# GENERADORA_V1_5.net
KiCad netlist of a schematic drawn in Altium Designer
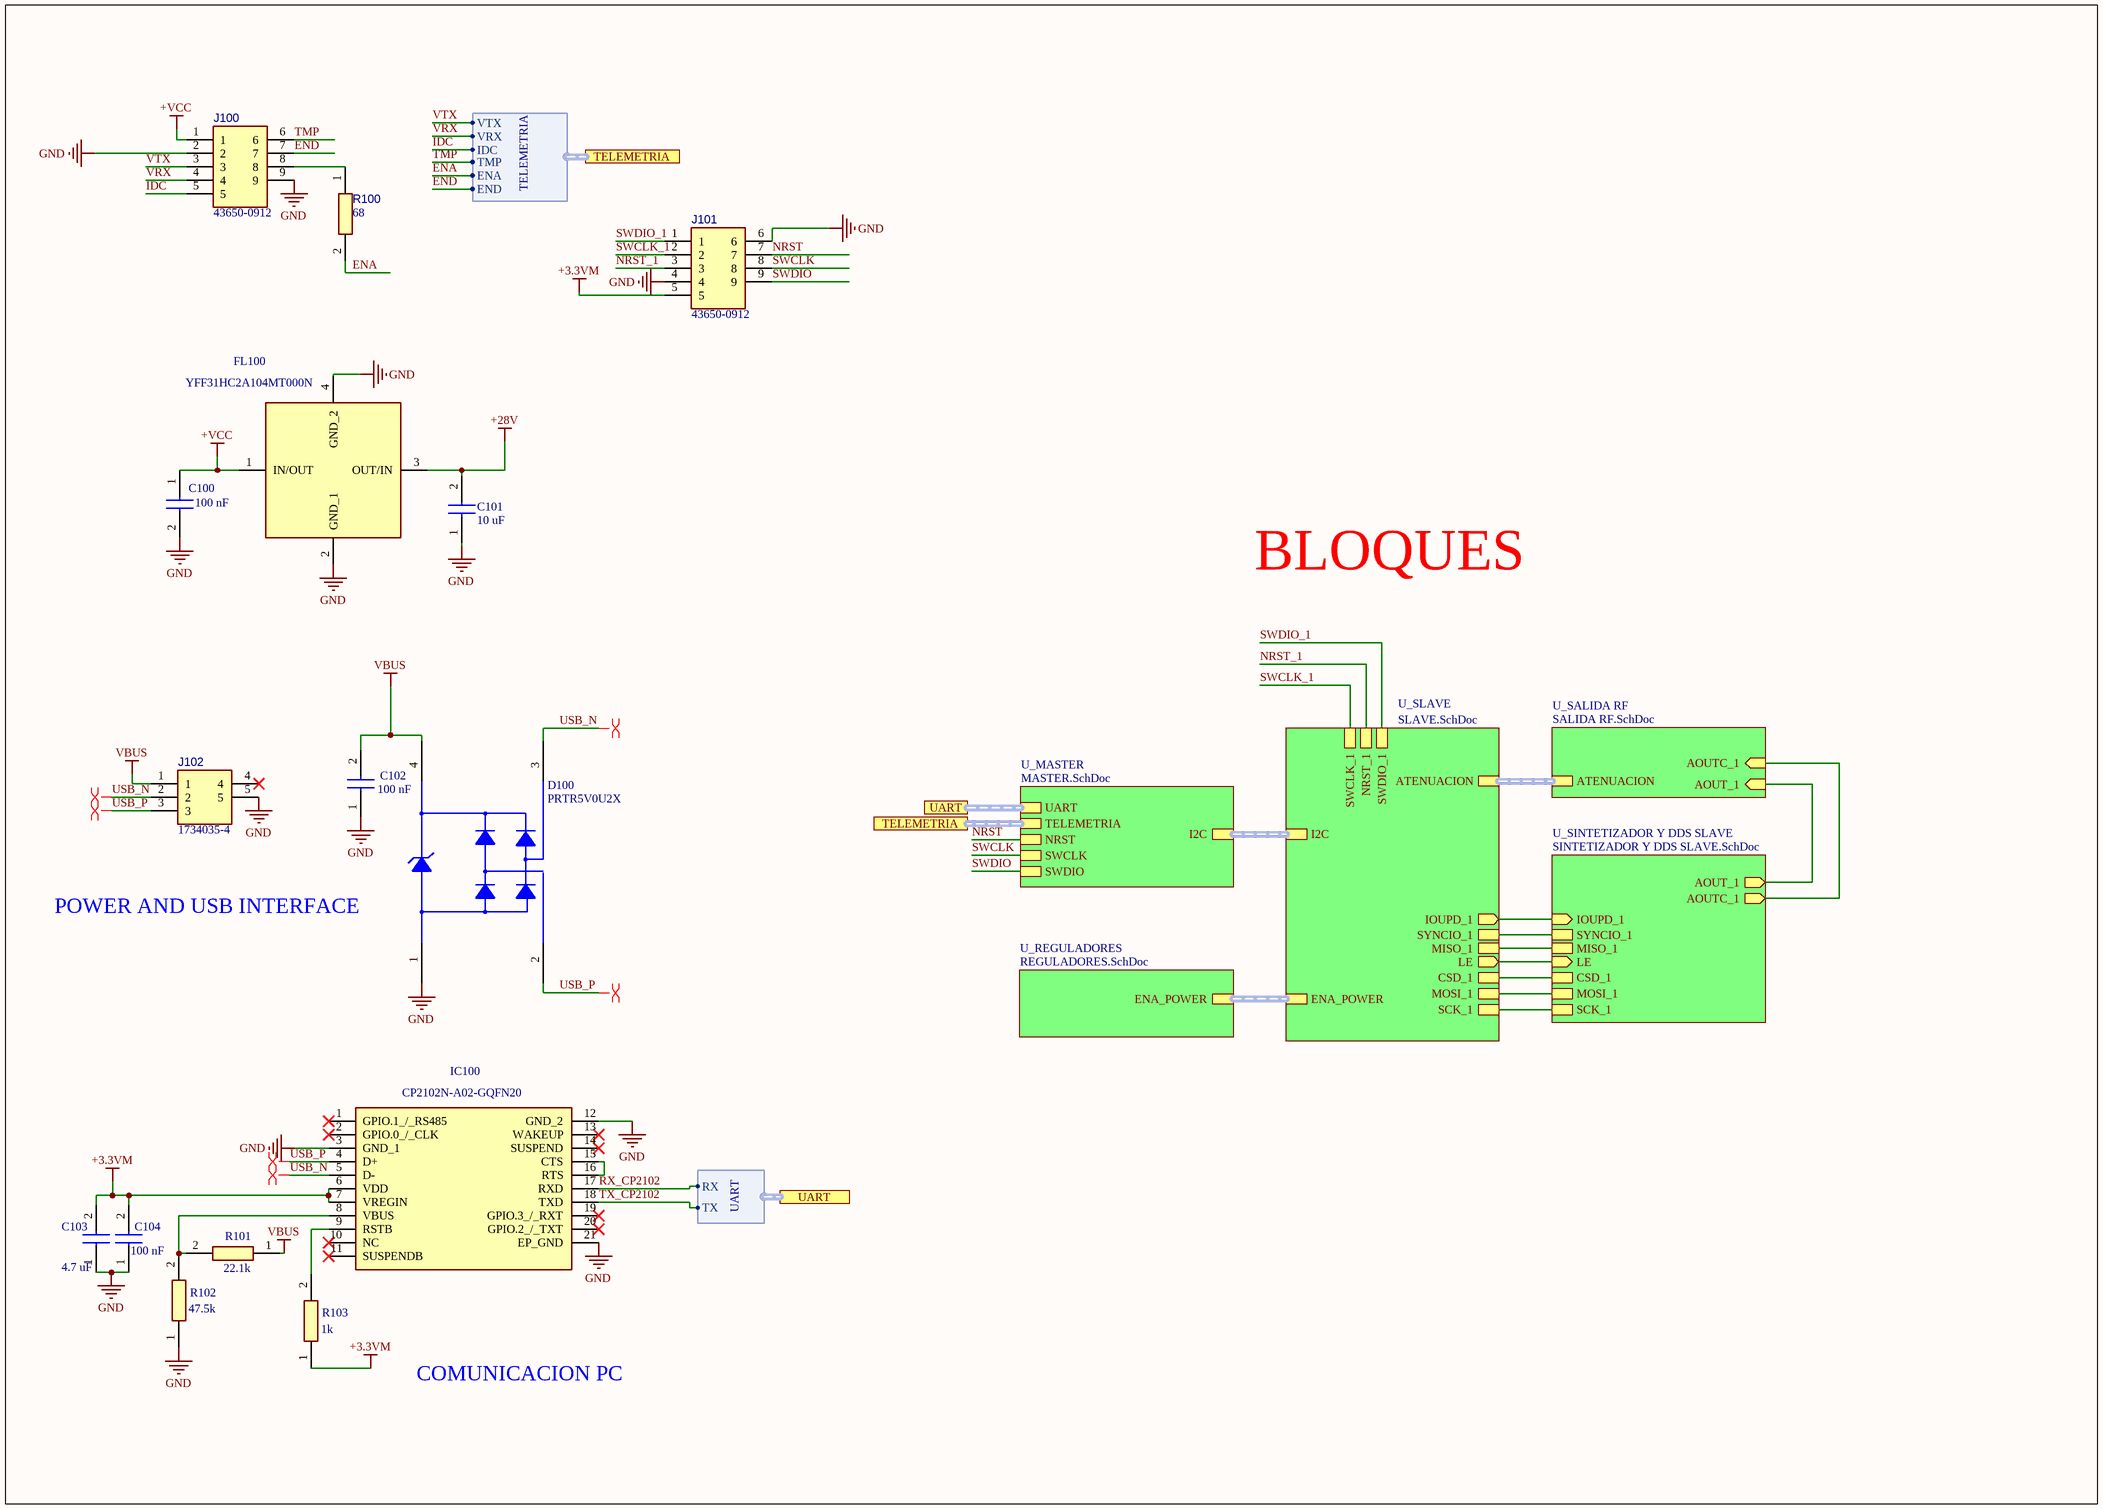
[diagram p0: GENERADORA V1.5.SchDoc]

(export (version "E")
  (design (tool "Eeschema 10.0.6"))
  (components
    (comp (ref "C100")
      (value "100 nF")
      (footprint "SamacSys:CAPC3216X94N")
      (description "Capacitor")
      (fields
        (field (name "MANUFACTURER_PART_NUMBER") "KAM31BR81H103KT")
        (field (name "MOUSER PART NUMBER") "581-KAM31BR81H103KT")
      )
      (libsource (lib "LIBRERIA_GEN_V2.0") (part "KAM31BR81H103KT"))
    )
    (comp (ref "C101")
      (value "10 uF")
      (footprint "SamacSys:CAPC3216X94N")
      (description "Capacitor")
      (fields
        (field (name "MANUFACTURER_PART_NUMBER") "KAM31BR81H103KT")
        (field (name "MOUSER PART NUMBER") "581-KAM31BR81H103KT")
      )
      (libsource (lib "LIBRERIA_GEN_V2.0") (part "KAM31BR81H103KT"))
    )
    (comp (ref "C102")
      (value "100 nF")
      (footprint "SamacSys:CAPC3216X94N")
      (description "Capacitor")
      (fields
        (field (name "MANUFACTURER_PART_NUMBER") "KAM31BR81H103KT")
        (field (name "MOUSER PART NUMBER") "581-KAM31BR81H103KT")
      )
      (libsource (lib "LIBRERIA_GEN_V2.0") (part "KAM31BR81H103KT"))
    )
    (comp (ref "C103")
      (value "4.7 uF")
      (footprint "SamacSys:C0603")
      (description "Capacitor")
      (fields (field (name "MANUFACTURER_PART_NUMBER") "C0603H470J5GACTU"))
      (libsource (lib "LIBRERIA_GEN_V2.0") (part "C0603H470J5GACTU"))
    )
    (comp (ref "C104")
      (value "100 nF")
      (footprint "SamacSys:C0603")
      (description "Capacitor")
      (fields (field (name "MANUFACTURER_PART_NUMBER") "C0603H470J5GACTU"))
      (libsource (lib "LIBRERIA_GEN_V2.0") (part "C0603H470J5GACTU"))
    )
    (comp (ref "D100")
      (value "PRTR5V0U2X")
      (footprint "AP4-00001")
      (description "Double rail-to-rail USB ESD protection diode")
      (fields (field (name "MANUFACTURER") "Philips"))
      (libsource (lib "SAM4S_Xplained_Pro") (part "PRTR5V0U2X"))
    )
    (comp (ref "FL100")
      (value "YFF31HC2A104MT000N")
      (footprint "SamacSys:YFF31HC2A104MT000N")
      (description "Filter")
      (fields (field (name "MOUSER PART NUMBER") "810-YFF31HC2A104MTHN"))
      (libsource (lib "LIBRERIA_GEN_V2.0") (part "YFF31HC2A104MT000N"))
    )
    (comp (ref "IC100")
      (value "CP2102N-A02-GQFN20")
      (footprint "SamacSys:CP2102NA02GQFN20")
      (description "Integrated Circuit")
      (fields (field (name "MOUSER PART NUMBER") "634-CP2102NA02GQFN20"))
      (libsource (lib "LIBRERIA_GEN_V2.0") (part "CP2102N-A02-GQFN20"))
    )
    (comp (ref "J100")
      (value "43650-0912")
      (footprint "SamacSys:43650-09(12,13,14)")
      (description "Connector")
      (fields (field (name "MOUSER PART NUMBER") "538-43650-0912"))
      (libsource (lib "*") (part "43650-0912"))
    )
    (comp (ref "J101")
      (value "43650-0912")
      (footprint "SamacSys:43650-09(12,13,14)")
      (description "Connector")
      (fields (field (name "MOUSER PART NUMBER") "538-43650-0912"))
      (libsource (lib "*") (part "43650-0912"))
    )
    (comp (ref "J102")
      (value "1734035-4")
      (footprint "SamacSys:1734035-2USB")
      (description "Connector")
      (fields (field (name "MOUSER PART NUMBER") "571-1734035-4"))
      (libsource (lib "SamacSys") (part "1734035-4"))
    )
    (comp (ref "R100")
      (value "68")
      (footprint "SamacSys:RESC1608X55N")
      (description "Resistor")
      (fields
        (field (name "MANUFACTURER_PART_NUMBER") "CR0603-FX-1431ELF")
        (field (name "MOUSER PART NUMBER") "652-CR0603FX-1431ELF")
      )
      (libsource (lib "*") (part "CR0603-FX-1431ELF"))
    )
    (comp (ref "R101")
      (value "22.1k")
      (footprint "SamacSys:RESC1608X55N")
      (description "Resistor")
      (fields
        (field (name "MANUFACTURER_PART_NUMBER") "CR0603-FX-1431ELF")
        (field (name "MOUSER PART NUMBER") "652-CR0603FX-1431ELF")
      )
      (libsource (lib "") (part "CR0603-FX-1431ELF_1"))
    )
    (comp (ref "R102")
      (value "47.5k")
      (footprint "SamacSys:RESC1608X55N")
      (description "Resistor")
      (fields
        (field (name "MANUFACTURER_PART_NUMBER") "CR0603-FX-1431ELF")
        (field (name "MOUSER PART NUMBER") "652-CR0603FX-1431ELF")
      )
      (libsource (lib "LIBRERIA_GEN_V2.0") (part "CR0603-FX-1431ELF"))
    )
    (comp (ref "R103")
      (value "1k")
      (footprint "SamacSys:RESC1608X55N")
      (description "Resistor")
      (fields
        (field (name "MANUFACTURER_PART_NUMBER") "CR0603-FX-1431ELF")
        (field (name "MOUSER PART NUMBER") "652-CR0603FX-1431ELF")
      )
      (libsource (lib "LIBRERIA_GEN_V2.0") (part "CR0603-FX-1431ELF"))
    )
  )
  (nets
    (net (code "4") (name "+3.3VM") (class "Default")
      (node (ref "C103") (pin "2") (pinfunction "2_2") (pintype "passive"))
      (node (ref "C104") (pin "2") (pinfunction "2_2") (pintype "passive"))
      (node (ref "IC100") (pin "6") (pinfunction "VDD_6") (pintype "passive"))
      (node (ref "IC100") (pin "7") (pinfunction "VREGIN_7") (pintype "passive"))
      (node (ref "J101") (pin "5") (pinfunction "5_5") (pintype "passive"))
      (node (ref "R103") (pin "1") (pinfunction "1_1") (pintype "passive"))
    )
    (net (code "5") (name "+28V") (class "Default")
      (node (ref "C101") (pin "2") (pinfunction "2_2") (pintype "passive"))
      (node (ref "FL100") (pin "3") (pinfunction "OUT/IN_3") (pintype "passive"))
    )
    (net (code "6") (name "+VCC") (class "Default")
      (node (ref "C100") (pin "1") (pinfunction "1_1") (pintype "passive"))
      (node (ref "FL100") (pin "1") (pinfunction "IN/OUT_1") (pintype "passive"))
      (node (ref "J100") (pin "1") (pinfunction "1_1") (pintype "passive"))
    )
    (net (code "11") (name "/ENA") (class "Default")
      (node (ref "R100") (pin "2") (pinfunction "2_2") (pintype "passive"))
    )
    (net (code "13") (name "/END") (class "Default")
      (node (ref "J100") (pin "7") (pinfunction "7_7") (pintype "passive"))
    )
    (net (code "15") (name "/IDC") (class "Default")
      (node (ref "J100") (pin "5") (pinfunction "5_5") (pintype "passive"))
    )
    (net (code "20") (name "/NRST") (class "Default")
      (node (ref "J101") (pin "7") (pinfunction "7_7") (pintype "passive"))
    )
    (net (code "21") (name "/NRST_1") (class "Default")
      (node (ref "J101") (pin "3") (pinfunction "3_3") (pintype "passive"))
    )
    (net (code "22") (name "/RX_CP2102") (class "Default")
      (node (ref "IC100") (pin "17") (pinfunction "RXD_17") (pintype "passive"))
    )
    (net (code "24") (name "/SWCLK") (class "Default")
      (node (ref "J101") (pin "8") (pinfunction "8_8") (pintype "passive"))
    )
    (net (code "25") (name "/SWCLK_1") (class "Default")
      (node (ref "J101") (pin "2") (pinfunction "2_2") (pintype "passive"))
    )
    (net (code "26") (name "/SWDIO") (class "Default")
      (node (ref "J101") (pin "9") (pinfunction "9_9") (pintype "passive"))
    )
    (net (code "27") (name "/SWDIO_1") (class "Default")
      (node (ref "J101") (pin "1") (pinfunction "1_1") (pintype "passive"))
    )
    (net (code "29") (name "/TMP") (class "Default")
      (node (ref "J100") (pin "6") (pinfunction "6_6") (pintype "passive"))
    )
    (net (code "30") (name "/TX_CP2102") (class "Default")
      (node (ref "IC100") (pin "18") (pinfunction "TXD_18") (pintype "passive"))
    )
    (net (code "32") (name "/USB_N") (class "Default")
      (node (ref "D100") (pin "3") (pinfunction "I/O_2_3") (pintype "passive"))
      (node (ref "IC100") (pin "5") (pinfunction "D-_5") (pintype "passive"))
      (node (ref "J102") (pin "2") (pinfunction "2_2") (pintype "passive"))
    )
    (net (code "33") (name "/USB_P") (class "Default")
      (node (ref "D100") (pin "2") (pinfunction "I/O_1_2") (pintype "passive"))
      (node (ref "IC100") (pin "4") (pinfunction "D+_4") (pintype "passive"))
      (node (ref "J102") (pin "3") (pinfunction "3_3") (pintype "passive"))
    )
    (net (code "34") (name "/VRX") (class "Default")
      (node (ref "J100") (pin "4") (pinfunction "4_4") (pintype "passive"))
    )
    (net (code "35") (name "/VTX") (class "Default")
      (node (ref "J100") (pin "3") (pinfunction "3_3") (pintype "passive"))
    )
    (net (code "38") (name "GND") (class "Default")
      (node (ref "C100") (pin "2") (pinfunction "2_2") (pintype "passive"))
      (node (ref "C101") (pin "1") (pinfunction "1_1") (pintype "passive"))
      (node (ref "C102") (pin "1") (pinfunction "1_1") (pintype "passive"))
      (node (ref "C103") (pin "1") (pinfunction "1_1") (pintype "passive"))
      (node (ref "C104") (pin "1") (pinfunction "1_1") (pintype "passive"))
      (node (ref "D100") (pin "1") (pinfunction "GND_1") (pintype "passive"))
      (node (ref "FL100") (pin "2") (pinfunction "GND_1_2") (pintype "passive"))
      (node (ref "FL100") (pin "4") (pinfunction "GND_2_4") (pintype "passive"))
      (node (ref "IC100") (pin "12") (pinfunction "GND_2_12") (pintype "passive"))
      (node (ref "IC100") (pin "21") (pinfunction "EP_GND_21") (pintype "passive"))
      (node (ref "IC100") (pin "3") (pinfunction "GND_1_3") (pintype "passive"))
      (node (ref "J100") (pin "2") (pinfunction "2_2") (pintype "passive"))
      (node (ref "J100") (pin "9") (pinfunction "9_9") (pintype "passive"))
      (node (ref "J101") (pin "4") (pinfunction "4_4") (pintype "passive"))
      (node (ref "J101") (pin "6") (pinfunction "6_6") (pintype "passive"))
      (node (ref "J102") (pin "5") (pinfunction "5_5") (pintype "passive"))
      (node (ref "R102") (pin "1") (pinfunction "1_1") (pintype "passive"))
    )
    (net (code "39") (name "Net-(IC100-CTS)") (class "Default")
      (node (ref "IC100") (pin "15") (pinfunction "CTS_15") (pintype "passive"))
      (node (ref "IC100") (pin "16") (pinfunction "RTS_16") (pintype "passive"))
    )
    (net (code "40") (name "Net-(IC100-RSTB)") (class "Default")
      (node (ref "IC100") (pin "9") (pinfunction "RSTB_9") (pintype "passive"))
      (node (ref "R103") (pin "2") (pinfunction "2_2") (pintype "passive"))
    )
    (net (code "41") (name "Net-(IC100-VBUS)") (class "Default")
      (node (ref "IC100") (pin "8") (pinfunction "VBUS_8") (pintype "passive"))
      (node (ref "R101") (pin "2") (pinfunction "2_2") (pintype "passive"))
      (node (ref "R102") (pin "2") (pinfunction "2_2") (pintype "passive"))
    )
    (net (code "42") (name "Net-(J100-Pad8)") (class "Default")
      (node (ref "J100") (pin "8") (pinfunction "8_8") (pintype "passive"))
      (node (ref "R100") (pin "1") (pinfunction "1_1") (pintype "passive"))
    )
    (net (code "43") (name "VBUS") (class "Default")
      (node (ref "C102") (pin "2") (pinfunction "2_2") (pintype "passive"))
      (node (ref "D100") (pin "4") (pinfunction "VCC_4") (pintype "passive"))
      (node (ref "J102") (pin "1") (pinfunction "1_1") (pintype "passive"))
      (node (ref "R101") (pin "1") (pinfunction "1_1") (pintype "passive"))
    )
    (net (code "44") (name "unconnected-(IC100-GPIO.0_{slash}_CLK-Pad2)") (class "Default")
      (node (ref "IC100") (pin "2") (pinfunction "GPIO.0_/_CLK_2") (pintype "passive+no_connect"))
    )
    (net (code "45") (name "unconnected-(IC100-GPIO.1_{slash}_RS485-Pad1)") (class "Default")
      (node (ref "IC100") (pin "1") (pinfunction "GPIO.1_/_RS485_1") (pintype "passive+no_connect"))
    )
    (net (code "46") (name "unconnected-(IC100-GPIO.2_{slash}_TXT-Pad20)") (class "Default")
      (node (ref "IC100") (pin "20") (pinfunction "GPIO.2_/_TXT_20") (pintype "passive+no_connect"))
    )
    (net (code "47") (name "unconnected-(IC100-GPIO.3_{slash}_RXT-Pad19)") (class "Default")
      (node (ref "IC100") (pin "19") (pinfunction "GPIO.3_/_RXT_19") (pintype "passive+no_connect"))
    )
    (net (code "48") (name "unconnected-(IC100-NC-Pad10)") (class "Default")
      (node (ref "IC100") (pin "10") (pinfunction "NC_10") (pintype "passive+no_connect"))
    )
    (net (code "49") (name "unconnected-(IC100-SUSPEND-Pad14)") (class "Default")
      (node (ref "IC100") (pin "14") (pinfunction "SUSPEND_14") (pintype "passive+no_connect"))
    )
    (net (code "50") (name "unconnected-(IC100-SUSPENDB-Pad11)") (class "Default")
      (node (ref "IC100") (pin "11") (pinfunction "SUSPENDB_11") (pintype "passive+no_connect"))
    )
    (net (code "51") (name "unconnected-(IC100-WAKEUP-Pad13)") (class "Default")
      (node (ref "IC100") (pin "13") (pinfunction "WAKEUP_13") (pintype "passive+no_connect"))
    )
    (net (code "52") (name "unconnected-(J102-Pad4)") (class "Default")
      (node (ref "J102") (pin "4") (pinfunction "4_4") (pintype "passive+no_connect"))
    )
  )
)
